# krajBB-Moj_i__Matej_gerber.net
KiCad netlist of a schematic drawn in EAGLE
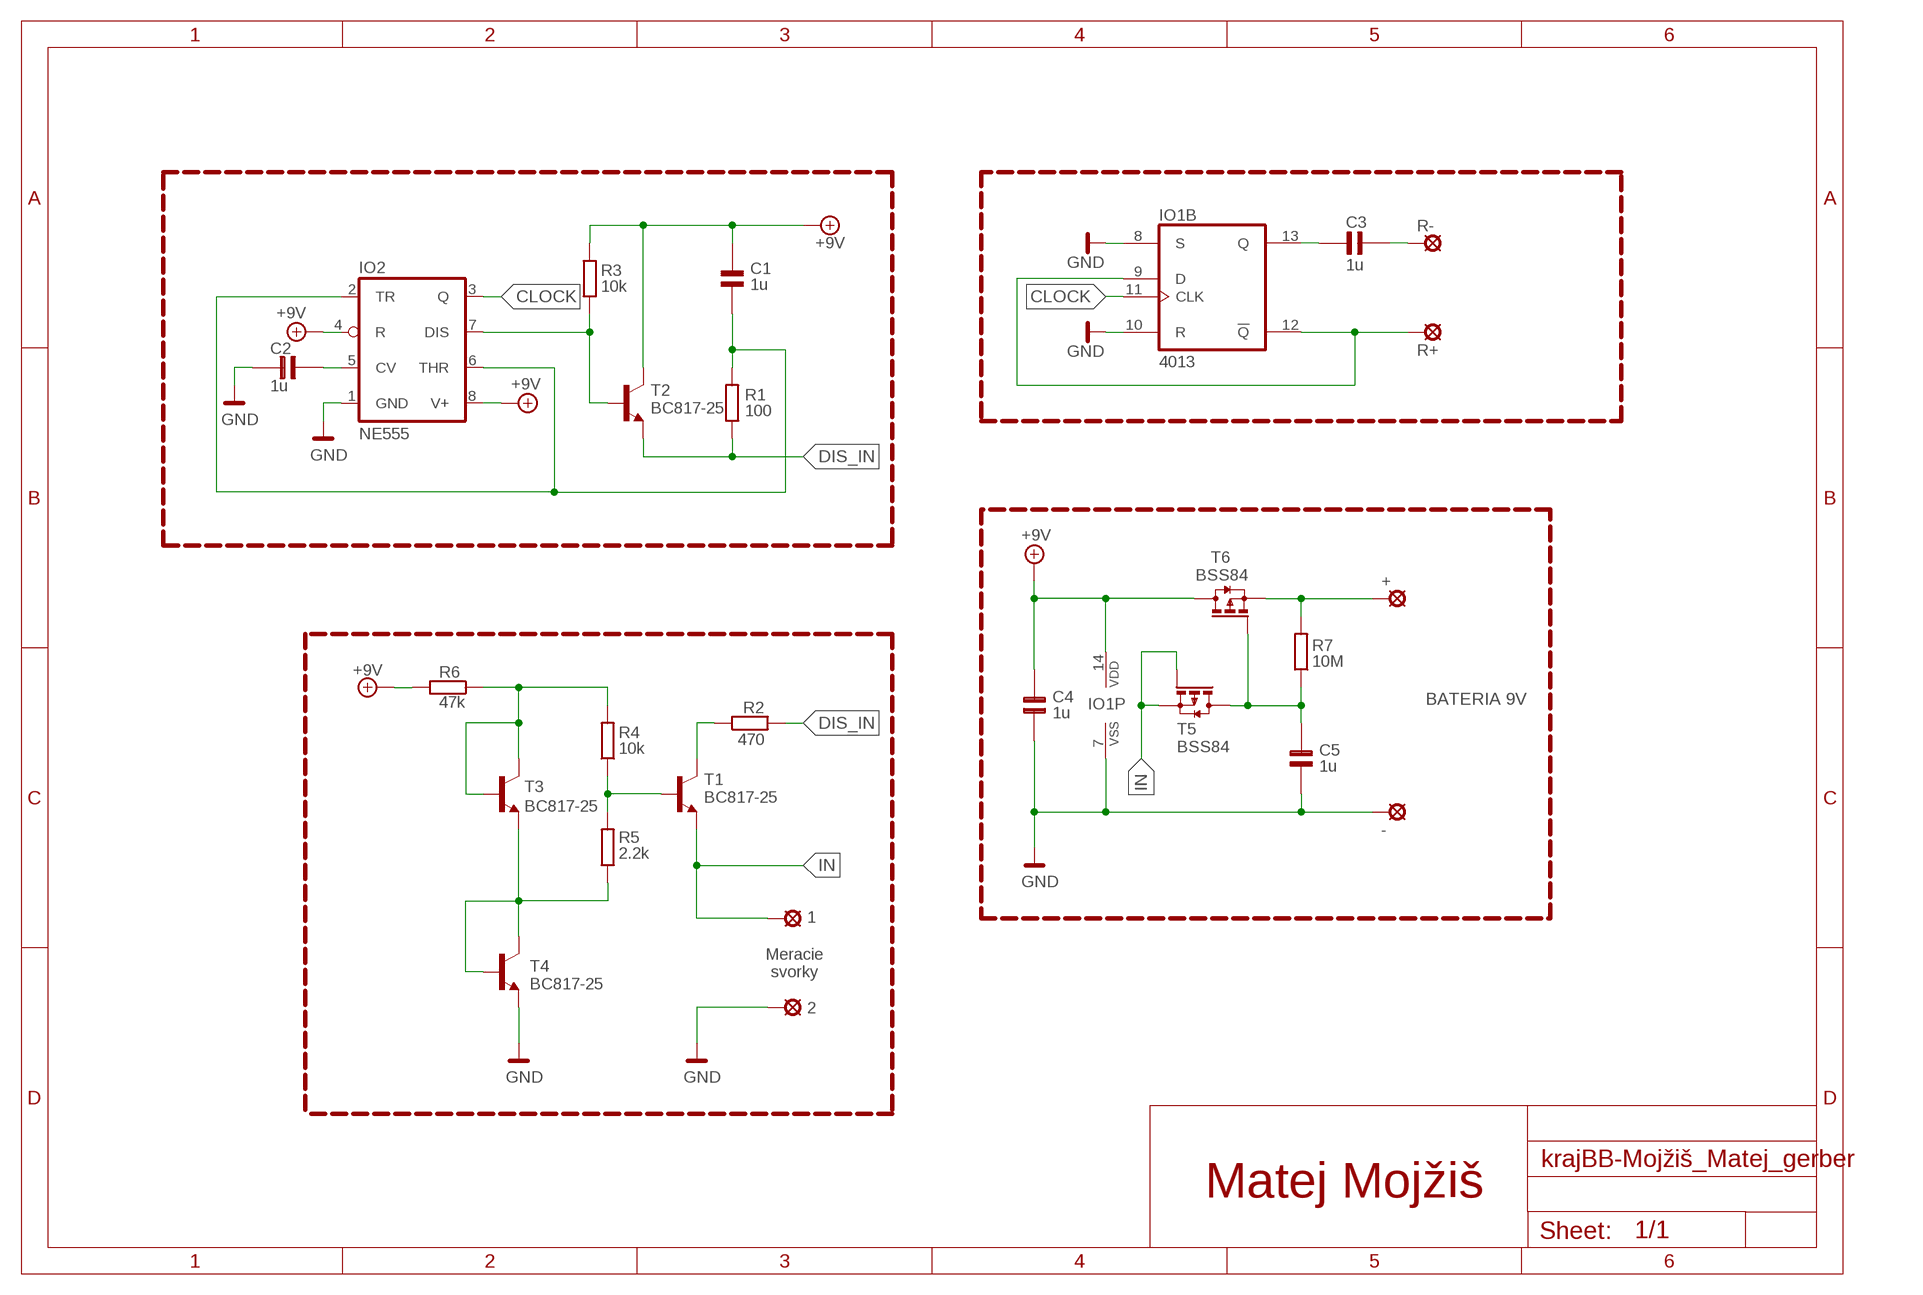
[diagram p0: schematic, sheet 1]

(export (version "E")
  (design (tool "Eeschema 10.0.6"))
  (components
    (comp (ref "+")
      (value "SMD3X3")
      (footprint "eagle-import:SMD3X3")
      (libsource (lib "eagle-import") (part "SMD3X3"))
    )
    (comp (ref "-")
      (value "SMD3X3")
      (footprint "eagle-import:SMD3X3")
      (libsource (lib "eagle-import") (part "SMD3X3"))
    )
    (comp (ref "1")
      (value "SMD3X3")
      (footprint "eagle-import:SMD3X3")
      (libsource (lib "eagle-import") (part "SMD3X3"))
    )
    (comp (ref "2")
      (value "SMD3X3")
      (footprint "eagle-import:SMD3X3")
      (libsource (lib "eagle-import") (part "SMD3X3"))
    )
    (comp (ref "C1")
      (value "1u")
      (footprint "eagle-import:1206")
      (libsource (lib "eagle-import") (part "C1206TOP"))
    )
    (comp (ref "C2")
      (value "1u")
      (footprint "eagle-import:1206")
      (libsource (lib "eagle-import") (part "C1206TOP"))
    )
    (comp (ref "C3")
      (value "1u")
      (footprint "eagle-import:1206")
      (libsource (lib "eagle-import") (part "C1206TOP"))
    )
    (comp (ref "C4")
      (value "1u")
      (footprint "eagle-import:1206")
      (libsource (lib "eagle-import") (part "C1206TOP"))
    )
    (comp (ref "C5")
      (value "1u")
      (footprint "eagle-import:1206")
      (libsource (lib "eagle-import") (part "C1206TOP"))
    )
    (comp (ref "IO1")
      (value "4013")
      (footprint "eagle-import:SO14")
      (libsource (lib "eagle-import") (part "4013D"))
    )
    (comp (ref "IO2")
      (value "NE555")
      (footprint "eagle-import:SO08")
      (libsource (lib "eagle-import") (part "555DNE"))
    )
    (comp (ref "R+")
      (value "SMD3X3")
      (footprint "eagle-import:SMD3X3")
      (libsource (lib "eagle-import") (part "SMD3X3"))
    )
    (comp (ref "R-")
      (value "SMD3X3")
      (footprint "eagle-import:SMD3X3")
      (libsource (lib "eagle-import") (part "SMD3X3"))
    )
    (comp (ref "R1")
      (value "100")
      (footprint "eagle-import:1206")
      (libsource (lib "eagle-import") (part "R1206TOP"))
    )
    (comp (ref "R2")
      (value "470")
      (footprint "eagle-import:1206")
      (libsource (lib "eagle-import") (part "R1206TOP"))
    )
    (comp (ref "R3")
      (value "10k")
      (footprint "eagle-import:1206")
      (libsource (lib "eagle-import") (part "R1206TOP"))
    )
    (comp (ref "R4")
      (value "10k")
      (footprint "eagle-import:1206")
      (libsource (lib "eagle-import") (part "R1206TOP"))
    )
    (comp (ref "R5")
      (value "2.2k")
      (footprint "eagle-import:1206")
      (libsource (lib "eagle-import") (part "R1206TOP"))
    )
    (comp (ref "R6")
      (value "47k")
      (footprint "eagle-import:1206")
      (libsource (lib "eagle-import") (part "R1206TOP"))
    )
    (comp (ref "R7")
      (value "10M")
      (footprint "eagle-import:1206")
      (libsource (lib "eagle-import") (part "R1206TOP"))
    )
    (comp (ref "T1")
      (value "BC817-25")
      (footprint "eagle-import:SOT23-BEC")
      (libsource (lib "eagle-import") (part "BC817SMD-25"))
    )
    (comp (ref "T2")
      (value "BC817-25")
      (footprint "eagle-import:SOT23-BEC")
      (libsource (lib "eagle-import") (part "BC817SMD-25"))
    )
    (comp (ref "T3")
      (value "BC817-25")
      (footprint "eagle-import:SOT23-BEC")
      (libsource (lib "eagle-import") (part "BC817SMD-25"))
    )
    (comp (ref "T4")
      (value "BC817-25")
      (footprint "eagle-import:SOT23-BEC")
      (libsource (lib "eagle-import") (part "BC817SMD-25"))
    )
    (comp (ref "T5")
      (value "BSS84")
      (footprint "eagle-import:SOT23")
      (libsource (lib "eagle-import") (part "BSS84"))
    )
    (comp (ref "T6")
      (value "BSS84")
      (footprint "eagle-import:SOT23")
      (libsource (lib "eagle-import") (part "BSS84"))
    )
  )
  (nets
    (net (code "1") (name "+9V") (class "Default")
      (node (ref "C1") (pin "2") (pinfunction "2_2") (pintype "passive"))
      (node (ref "C4") (pin "2") (pinfunction "2_2") (pintype "passive"))
      (node (ref "IO1") (pin "14") (pinfunction "VDD_14") (pintype "power_in"))
      (node (ref "IO2") (pin "4") (pinfunction "R_4") (pintype "input"))
      (node (ref "IO2") (pin "8") (pinfunction "V+_8") (pintype "power_in"))
      (node (ref "R3") (pin "2") (pinfunction "2_2") (pintype "passive"))
      (node (ref "R6") (pin "2") (pinfunction "2_2") (pintype "passive"))
      (node (ref "T2") (pin "C") (pinfunction "C_C") (pintype "passive"))
      (node (ref "T6") (pin "3") (pinfunction "D_3") (pintype "passive"))
    )
    (net (code "2") (name "CLOCK") (class "Default")
      (node (ref "IO1") (pin "11") (pinfunction "CLK_11") (pintype "input"))
      (node (ref "IO2") (pin "3") (pinfunction "Q_3") (pintype "output"))
    )
    (net (code "3") (name "DIS_IN") (class "Default")
      (node (ref "R1") (pin "1") (pinfunction "1_1") (pintype "passive"))
      (node (ref "R2") (pin "2") (pinfunction "2_2") (pintype "passive"))
      (node (ref "T2") (pin "E") (pinfunction "E_E") (pintype "passive"))
    )
    (net (code "4") (name "GND") (class "Default")
      (node (ref "-") (pin "P$1") (pinfunction "MP_P$1") (pintype "passive"))
      (node (ref "2") (pin "P$1") (pinfunction "MP_P$1") (pintype "passive"))
      (node (ref "C2") (pin "1") (pinfunction "1_1") (pintype "passive"))
      (node (ref "C4") (pin "1") (pinfunction "1_1") (pintype "passive"))
      (node (ref "C5") (pin "1") (pinfunction "1_1") (pintype "passive"))
      (node (ref "IO1") (pin "10") (pinfunction "R_10") (pintype "input"))
      (node (ref "IO1") (pin "7") (pinfunction "VSS_7") (pintype "power_in"))
      (node (ref "IO1") (pin "8") (pinfunction "S_8") (pintype "input"))
      (node (ref "IO2") (pin "1") (pinfunction "GND_1") (pintype "power_in"))
      (node (ref "T4") (pin "E") (pinfunction "E_E") (pintype "passive"))
    )
    (net (code "5") (name "IN") (class "Default")
      (node (ref "1") (pin "P$1") (pinfunction "MP_P$1") (pintype "passive"))
      (node (ref "T1") (pin "E") (pinfunction "E_E") (pintype "passive"))
      (node (ref "T5") (pin "1") (pinfunction "G_1") (pintype "passive"))
      (node (ref "T5") (pin "2") (pinfunction "S_2") (pintype "passive"))
    )
    (net (code "6") (name "Net-(+-MP)") (class "Default")
      (node (ref "+") (pin "P$1") (pinfunction "MP_P$1") (pintype "passive"))
      (node (ref "R7") (pin "2") (pinfunction "2_2") (pintype "passive"))
      (node (ref "T6") (pin "2") (pinfunction "S_2") (pintype "passive"))
    )
    (net (code "7") (name "Net-(IO1B-D)") (class "Default")
      (node (ref "IO1") (pin "12") (pinfunction "~{Q}_12") (pintype "output"))
      (node (ref "IO1") (pin "9") (pinfunction "D_9") (pintype "input"))
      (node (ref "R+") (pin "P$1") (pinfunction "MP_P$1") (pintype "passive"))
    )
    (net (code "8") (name "Net-(IO1B-Q)") (class "Default")
      (node (ref "C3") (pin "1") (pinfunction "1_1") (pintype "passive"))
      (node (ref "IO1") (pin "13") (pinfunction "Q_13") (pintype "output"))
    )
    (net (code "9") (name "Net-(IO2-CV)") (class "Default")
      (node (ref "C2") (pin "2") (pinfunction "2_2") (pintype "passive"))
      (node (ref "IO2") (pin "5") (pinfunction "CV_5") (pintype "input"))
    )
    (net (code "10") (name "Net-(IO2-DIS)") (class "Default")
      (node (ref "IO2") (pin "7") (pinfunction "DIS_7") (pintype "input"))
      (node (ref "R3") (pin "1") (pinfunction "1_1") (pintype "passive"))
      (node (ref "T2") (pin "B") (pinfunction "B_B") (pintype "passive"))
    )
    (net (code "11") (name "Net-(IO2-THR)") (class "Default")
      (node (ref "C1") (pin "1") (pinfunction "1_1") (pintype "passive"))
      (node (ref "IO2") (pin "2") (pinfunction "TR_2") (pintype "input"))
      (node (ref "IO2") (pin "6") (pinfunction "THR_6") (pintype "input"))
      (node (ref "R1") (pin "2") (pinfunction "2_2") (pintype "passive"))
    )
    (net (code "12") (name "Net-(R--MP)") (class "Default")
      (node (ref "C3") (pin "2") (pinfunction "2_2") (pintype "passive"))
      (node (ref "R-") (pin "P$1") (pinfunction "MP_P$1") (pintype "passive"))
    )
    (net (code "13") (name "Net-(R2-Pad1)") (class "Default")
      (node (ref "R2") (pin "1") (pinfunction "1_1") (pintype "passive"))
      (node (ref "T1") (pin "C") (pinfunction "C_C") (pintype "passive"))
    )
    (net (code "14") (name "Net-(R4-Pad1)") (class "Default")
      (node (ref "R4") (pin "1") (pinfunction "1_1") (pintype "passive"))
      (node (ref "R5") (pin "2") (pinfunction "2_2") (pintype "passive"))
      (node (ref "T1") (pin "B") (pinfunction "B_B") (pintype "passive"))
    )
    (net (code "15") (name "Net-(R4-Pad2)") (class "Default")
      (node (ref "R4") (pin "2") (pinfunction "2_2") (pintype "passive"))
      (node (ref "R6") (pin "1") (pinfunction "1_1") (pintype "passive"))
      (node (ref "T3") (pin "B") (pinfunction "B_B") (pintype "passive"))
      (node (ref "T3") (pin "C") (pinfunction "C_C") (pintype "passive"))
    )
    (net (code "16") (name "Net-(R5-Pad1)") (class "Default")
      (node (ref "R5") (pin "1") (pinfunction "1_1") (pintype "passive"))
      (node (ref "T3") (pin "E") (pinfunction "E_E") (pintype "passive"))
      (node (ref "T4") (pin "B") (pinfunction "B_B") (pintype "passive"))
      (node (ref "T4") (pin "C") (pinfunction "C_C") (pintype "passive"))
    )
    (net (code "17") (name "Net-(T5-D)") (class "Default")
      (node (ref "C5") (pin "2") (pinfunction "2_2") (pintype "passive"))
      (node (ref "R7") (pin "1") (pinfunction "1_1") (pintype "passive"))
      (node (ref "T5") (pin "3") (pinfunction "D_3") (pintype "passive"))
      (node (ref "T6") (pin "1") (pinfunction "G_1") (pintype "passive"))
    )
  )
)
